# sch_station_de_charge_r.net
KiCad netlist of a schematic drawn in Altium Designer
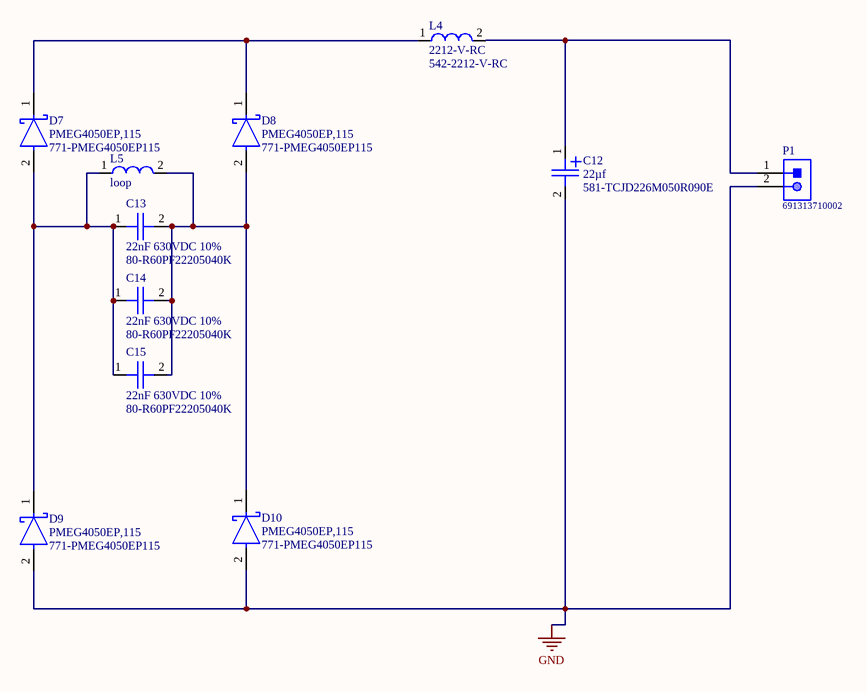
[diagram p0: sch_station_de_charge_r.SchDoc]

(export (version "E")
  (design (tool "Eeschema 10.0.6"))
  (components
    (comp (ref "C12")
      (value "22µf")
      (footprint "CAPPM7343X310N")
      (fields
        (field (name "MANUFACTURER") "Kyocera AVX")
        (field (name "MANUFACTURER PART NUMBER") "TCJD226M050R0090E")
        (field (name "SUPPLIER PART NUMBER 1") "581-TCJD226M050R090E")
      )
      (libsource (lib "station_de_charge_SchLib") (part "TCJD226M050R0090E"))
    )
    (comp (ref "C13")
      (value "22nF 630VDC 10%")
      (footprint "R60PF22205040K")
      (description "Cap Film 0.022uF 630V PET 10%( 13 X 4 X 9mm) Radial Wound 10mm 105C Automotive Bag")
      (fields
        (field (name "MANUFACTURER") "KEMET")
        (field (name "MANUFACTURER PART NUMBER") "R60PF22205040K")
        (field (name "SUPPLIER PART NUMBER 1") "80-R60PF22205040K")
      )
      (libsource (lib "station_de_charge_SchLib") (part "R60PF22205040K"))
    )
    (comp (ref "C14")
      (value "22nF 630VDC 10%")
      (footprint "R60PF22205040K")
      (description "Cap Film 0.022uF 630V PET 10%( 13 X 4 X 9mm) Radial Wound 10mm 105C Automotive Bag")
      (fields
        (field (name "MANUFACTURER") "KEMET")
        (field (name "MANUFACTURER PART NUMBER") "R60PF22205040K")
        (field (name "SUPPLIER PART NUMBER 1") "80-R60PF22205040K")
      )
      (libsource (lib "station_de_charge_SchLib") (part "R60PF22205040K"))
    )
    (comp (ref "C15")
      (value "22nF 630VDC 10%")
      (footprint "R60PF22205040K")
      (description "Cap Film 0.022uF 630V PET 10%( 13 X 4 X 9mm) Radial Wound 10mm 105C Automotive Bag")
      (fields
        (field (name "MANUFACTURER") "KEMET")
        (field (name "MANUFACTURER PART NUMBER") "R60PF22205040K")
        (field (name "SUPPLIER PART NUMBER 1") "80-R60PF22205040K")
      )
      (libsource (lib "station_de_charge_SchLib") (part "R60PF22205040K"))
    )
    (comp (ref "D7")
      (value "PMEG4050EP,115")
      (footprint "FP-SOD128-MFG")
      (description "DIODE SCHOTTKY 40V 5A SOD128")
      (fields
        (field (name "MANUFACTURER") "Nexperia")
        (field (name "SUPPLIER PART NUMBER 1") "771-PMEG4050EP115")
      )
      (libsource (lib "station_de_charge_SchLib") (part "PMEG4050EP,115"))
    )
    (comp (ref "D8")
      (value "PMEG4050EP,115")
      (footprint "FP-SOD128-MFG")
      (description "DIODE SCHOTTKY 40V 5A SOD128")
      (fields
        (field (name "MANUFACTURER") "Nexperia")
        (field (name "SUPPLIER PART NUMBER 1") "771-PMEG4050EP115")
      )
      (libsource (lib "station_de_charge_SchLib") (part "PMEG4050EP,115"))
    )
    (comp (ref "D9")
      (value "PMEG4050EP,115")
      (footprint "FP-SOD128-MFG")
      (description "DIODE SCHOTTKY 40V 5A SOD128")
      (fields
        (field (name "MANUFACTURER") "Nexperia")
        (field (name "SUPPLIER PART NUMBER 1") "771-PMEG4050EP115")
      )
      (libsource (lib "station_de_charge_SchLib") (part "PMEG4050EP,115"))
    )
    (comp (ref "D10")
      (value "PMEG4050EP,115")
      (footprint "FP-SOD128-MFG")
      (description "DIODE SCHOTTKY 40V 5A SOD128")
      (fields
        (field (name "MANUFACTURER") "Nexperia")
        (field (name "SUPPLIER PART NUMBER 1") "771-PMEG4050EP115")
      )
      (libsource (lib "station_de_charge_SchLib") (part "PMEG4050EP,115"))
    )
    (comp (ref "L4")
      (value "2212-V-RC")
      (footprint "IND_HCTI-220-5.8")
      (description "Inductor High Current Toroid 100uH/64uH 15% 1KHz 4.4A 56mOhm DCR RDL")
      (fields
        (field (name "MANUFACTURER") "Bourns JW Miller")
        (field (name "TOLERANCE") "15%")
        (field (name "SUPPLIER PART NUMBER 1") "542-2212-V-RC")
      )
      (libsource (lib "station_de_charge_SchLib") (part "2212-V-RC"))
    )
    (comp (ref "L5")
      (value "loop")
      (footprint "loop")
      (libsource (lib "station_de_charge_SchLib") (part "loop"))
    )
    (comp (ref "P1")
      (value "691313710002")
      (footprint "691313710002")
      (description "Serie 3137 - 5.00mm Close Horizontal PCB Header WR-TBL, 2 pin")
      (fields (field (name "MANUFACTURER") "Wurth Elektronik") (field (name "PUBLISHER") "WurthElektronik"))
      (libsource (lib "station_de_charge_SchLib") (part "CMP-1502-02048-1"))
    )
  )
  (nets
    (net (code "1") (name "GND") (class "Default")
      (node (ref "C12") (pin "2") (pinfunction "2_2") (pintype "passive"))
      (node (ref "D10") (pin "2") (pinfunction "A_2") (pintype "passive"))
      (node (ref "D9") (pin "2") (pinfunction "A_2") (pintype "passive"))
      (node (ref "P1") (pin "2") (pinfunction "2_2") (pintype "passive"))
    )
    (net (code "2") (name "Net-(C12-Pad1)") (class "Default")
      (node (ref "C12") (pin "1") (pinfunction "1_1") (pintype "passive"))
      (node (ref "L4") (pin "2") (pinfunction "2_2") (pintype "passive"))
      (node (ref "P1") (pin "1") (pinfunction "1_1") (pintype "passive"))
    )
    (net (code "3") (name "Net-(D7-A)") (class "Default")
      (node (ref "C13") (pin "1") (pinfunction "1_1") (pintype "passive"))
      (node (ref "C14") (pin "1") (pinfunction "1_1") (pintype "passive"))
      (node (ref "C15") (pin "1") (pinfunction "1_1") (pintype "passive"))
      (node (ref "D7") (pin "2") (pinfunction "A_2") (pintype "passive"))
      (node (ref "D9") (pin "1") (pinfunction "K_1") (pintype "passive"))
      (node (ref "L5") (pin "1") (pinfunction "1_1") (pintype "passive"))
    )
    (net (code "4") (name "Net-(D7-K)") (class "Default")
      (node (ref "D7") (pin "1") (pinfunction "K_1") (pintype "passive"))
      (node (ref "D8") (pin "1") (pinfunction "K_1") (pintype "passive"))
      (node (ref "L4") (pin "1") (pinfunction "1_1") (pintype "passive"))
    )
    (net (code "5") (name "Net-(D10-K)") (class "Default")
      (node (ref "C13") (pin "2") (pinfunction "2_2") (pintype "passive"))
      (node (ref "C14") (pin "2") (pinfunction "2_2") (pintype "passive"))
      (node (ref "C15") (pin "2") (pinfunction "2_2") (pintype "passive"))
      (node (ref "D10") (pin "1") (pinfunction "K_1") (pintype "passive"))
      (node (ref "D8") (pin "2") (pinfunction "A_2") (pintype "passive"))
      (node (ref "L5") (pin "2") (pinfunction "2_2") (pintype "passive"))
    )
  )
)
